# Mainsystem.net
KiCad netlist of a schematic drawn in Altium Designer
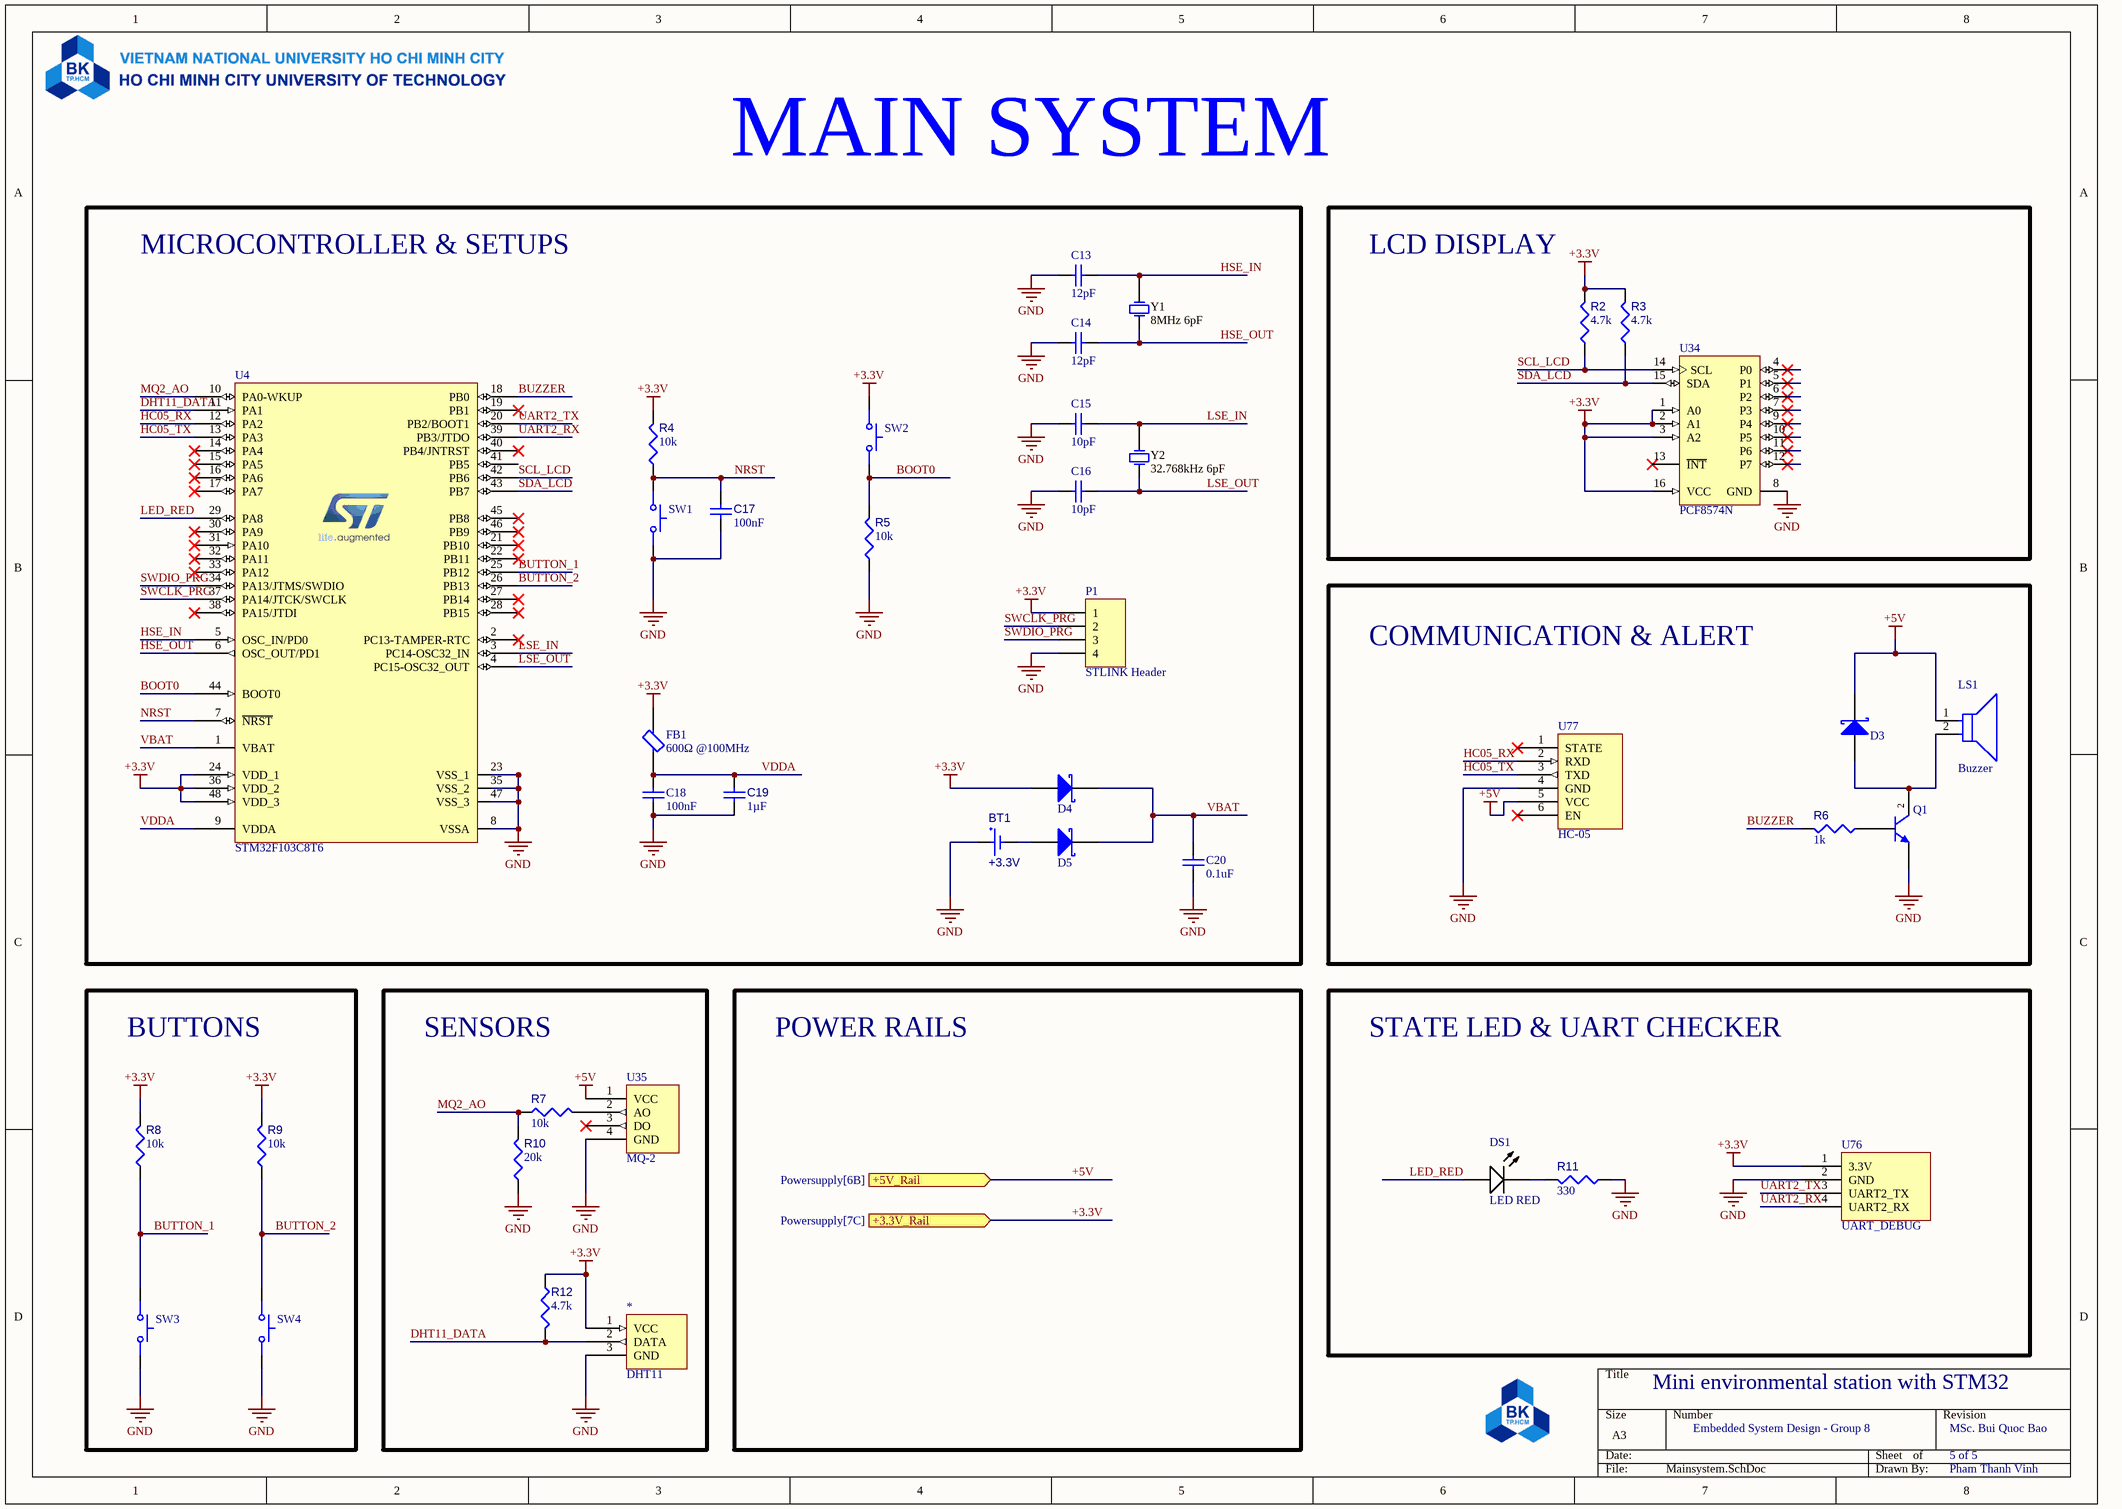
[diagram p0: Mainsystem.SchDoc]

(export (version "E")
  (design (tool "Eeschema 10.0.6"))
  (components
    (comp (ref "*")
      (value "DHT11")
      (footprint "HDR1X3")
      (description "vinh")
      (libsource (lib "HONG AN pham") (part "New symbol 1"))
    )
    (comp (ref "BT1")
      (value "+3.3V")
      (footprint "SEIK-MS621FE-FL11E-2_V")
      (description "MS Lihium Rechargeable Battery, 3 V, -20 to 60 degC, Tray")
      (libsource (lib "HONG AN pham") (part "CMP-00622-2"))
    )
    (comp (ref "C13")
      (value "12pF")
      (footprint "CAPC1608X90X35ML15T15")
      (description "Chip Capacitor, 1 uF, +/- 10%, 16 V, 0603 (1608 Metric)")
      (fields (field (name "TOLERANCE") "10%") (field (name "Comment") "Capacitor 1uF +/- 10% 16V 0603"))
      (libsource (lib "HONG AN pham") (part "CAP-NP-2"))
    )
    (comp (ref "C14")
      (value "12pF")
      (footprint "CAPC1608X90X35ML15T15")
      (description "Chip Capacitor, 1 uF, +/- 10%, 16 V, 0603 (1608 Metric)")
      (fields (field (name "TOLERANCE") "10%") (field (name "Comment") "Capacitor 1uF +/- 10% 16V 0603"))
      (libsource (lib "HONG AN pham") (part "CAP-NP-2"))
    )
    (comp (ref "C15")
      (value "10pF")
      (footprint "CAPC1608X90X35ML15T15")
      (description "Chip Capacitor, 1 uF, +/- 10%, 16 V, 0603 (1608 Metric)")
      (fields (field (name "TOLERANCE") "10%") (field (name "Comment") "Capacitor 1uF +/- 10% 16V 0603"))
      (libsource (lib "HONG AN pham") (part "CAP-NP-2"))
    )
    (comp (ref "C16")
      (value "10pF")
      (footprint "CAPC1608X90X35ML15T15")
      (description "Chip Capacitor, 1 uF, +/- 10%, 16 V, 0603 (1608 Metric)")
      (fields (field (name "TOLERANCE") "10%") (field (name "Comment") "Capacitor 1uF +/- 10% 16V 0603"))
      (libsource (lib "HONG AN pham") (part "CAP-NP-2"))
    )
    (comp (ref "C17")
      (value "100nF")
      (footprint "CAPC0402(1005)60_L")
      (description "Chip Capacitor, 100nF +/-20%, 10V, 0402, Thickness 0.6 mm")
      (fields (field (name "TOLERANCE") "20%") (field (name "Comment") "Capacitor 100nF +/-20% 10V 0402"))
      (libsource (lib "HONG AN pham") (part "CAP-NP-2"))
    )
    (comp (ref "C18")
      (value "100nF")
      (footprint "CAPC1608X90X35ML15T15")
      (description "Chip Capacitor, 1 uF, +/- 10%, 16 V, 0603 (1608 Metric)")
      (fields (field (name "TOLERANCE") "10%") (field (name "Comment") "Capacitor 1uF +/- 10% 16V 0603"))
      (libsource (lib "HONG AN pham") (part "CAP-NP-2"))
    )
    (comp (ref "C19")
      (value "1µF")
      (footprint "CAPC1608X90X35ML15T15")
      (description "Chip Capacitor, 1 uF, +/- 10%, 16 V, 0603 (1608 Metric)")
      (fields (field (name "TOLERANCE") "10%") (field (name "Comment") "Capacitor 1uF +/- 10% 16V 0603"))
      (libsource (lib "HONG AN pham") (part "CAP-NP-2"))
    )
    (comp (ref "C20")
      (value "0.1uF")
      (footprint "CAPC1608X90X35ML15T15")
      (description "Chip Capacitor, 1 uF, +/- 10%, 16 V, 0603 (1608 Metric)")
      (fields (field (name "TOLERANCE") "10%") (field (name "Comment") "Capacitor 1uF +/- 10% 16V 0603"))
      (libsource (lib "HONG AN pham") (part "CAP-NP-2"))
    )
    (comp (ref "D3")
      (value "B5819W")
      (footprint "MCC-SOD123_V")
      (description "Schottky Barrier Rectifier, 40 V, 1 A, -65 to 125 degC, 2-Pin SOD123, RoHS, Tape and Reel")
      (fields (field (name "MANUFACTURER") "Micro Commercial Components"))
      (libsource (lib "HONG AN pham") (part "DSKY-AK-2"))
    )
    (comp (ref "D4")
      (value "B5819W")
      (footprint "MCC-SOD123_V")
      (description "Schottky Barrier Rectifier, 40 V, 1 A, -65 to 125 degC, 2-Pin SOD123, RoHS, Tape and Reel")
      (fields (field (name "MANUFACTURER") "Micro Commercial Components"))
      (libsource (lib "HONG AN pham") (part "DSKY-AK-2"))
    )
    (comp (ref "D5")
      (value "B5819W")
      (footprint "MCC-SOD123_V")
      (description "Schottky Barrier Rectifier, 40 V, 1 A, -65 to 125 degC, 2-Pin SOD123, RoHS, Tape and Reel")
      (fields (field (name "MANUFACTURER") "Micro Commercial Components"))
      (libsource (lib "HONG AN pham") (part "DSKY-AK-2"))
    )
    (comp (ref "DS1")
      (value "LED RED")
      (footprint "EVRL-0402-2_V")
      (description "Chip LED, White, 5 V, 10 mA, 30 mW, -40 to 85 degC, 2-Pin SMD (0402), RoHS, Tape and Reel")
      (fields (field (name "POWER") "30mW") (field (name "MANUFACTURER") "Everlight Electronics"))
      (libsource (lib "HONG AN pham") (part "LED-WHITE-AK-2"))
    )
    (comp (ref "FB1")
      (value "600Ω @100MHz")
      (footprint "FP-BLM21-0_2-t0_85-e0_5-IPC_B")
      (description "Chip Ferrite Bead, 0805, 150Ω @ 100MHz, 0.21Ω, 25%, 600mA")
      (libsource (lib "Altium Content Vault") (part "5f30dd21d616792df468990f7003faa"))
    )
    (comp (ref "LS1")
      (value "Buzzer")
      (footprint "FP-CT-1205CL-SMT-TR-MFG")
      (libsource (lib "HONG AN pham") (part "1973c4b650225fd2ddacaff6b763965"))
    )
    (comp (ref "P1")
      (value "STLINK Header")
      (footprint "JP4")
      (description "Header, 4-Pin")
      (fields (field (name "PUBLISHER") "Altium Limited"))
      (libsource (lib "HONG AN pham") (part "Header 4H"))
    )
    (comp (ref "Q1")
      (value "MMBT2222A")
      (footprint "MMBT-SOT23")
      (description "TRANS NPN, 40V, 600MA, SOT23-3")
      (libsource (lib "HONG AN pham") (part "MMBT2222A"))
    )
    (comp (ref "R2")
      (value "4.7k")
      (footprint "RESC0402(1005)_L")
      (description "10K 0.063W 1% 0402 (1005 Metric)  SMD")
      (fields (field (name "POWER") "63mW") (field (name "TOLERANCE") "1%"))
      (libsource (lib "HONG AN pham") (part "10KR2F"))
    )
    (comp (ref "R3")
      (value "4.7k")
      (footprint "RESC0402(1005)_L")
      (description "10K 0.063W 1% 0402 (1005 Metric)  SMD")
      (fields (field (name "POWER") "63mW") (field (name "TOLERANCE") "1%"))
      (libsource (lib "HONG AN pham") (part "10KR2F"))
    )
    (comp (ref "R4")
      (value "10k")
      (footprint "RESC0402(1005)_L")
      (description "10K 0.063W 1% 0402 (1005 Metric)  SMD")
      (fields (field (name "POWER") "63mW") (field (name "TOLERANCE") "1%"))
      (libsource (lib "HONG AN pham") (part "10KR2F"))
    )
    (comp (ref "R5")
      (value "10k")
      (footprint "RESC0402(1005)_L")
      (description "10K 0.063W 1% 0402 (1005 Metric)  SMD")
      (fields (field (name "POWER") "63mW") (field (name "TOLERANCE") "1%"))
      (libsource (lib "HONG AN pham") (part "10KR2F"))
    )
    (comp (ref "R6")
      (value "1k")
      (footprint "RESC0402(1005)_L")
      (description "10K 0.063W 1% 0402 (1005 Metric)  SMD")
      (fields (field (name "POWER") "63mW") (field (name "TOLERANCE") "1%"))
      (libsource (lib "HONG AN pham") (part "10KR2F"))
    )
    (comp (ref "R7")
      (value "10k")
      (footprint "RESC0402(1005)_L")
      (description "10K 0.063W 1% 0402 (1005 Metric)  SMD")
      (fields (field (name "POWER") "63mW") (field (name "TOLERANCE") "1%"))
      (libsource (lib "HONG AN pham") (part "10KR2F"))
    )
    (comp (ref "R8")
      (value "10k")
      (footprint "RESC0402(1005)_L")
      (description "10K 0.063W 1% 0402 (1005 Metric)  SMD")
      (fields (field (name "POWER") "63mW") (field (name "TOLERANCE") "1%"))
      (libsource (lib "HONG AN pham") (part "10KR2F"))
    )
    (comp (ref "R9")
      (value "10k")
      (footprint "RESC0402(1005)_L")
      (description "10K 0.063W 1% 0402 (1005 Metric)  SMD")
      (fields (field (name "POWER") "63mW") (field (name "TOLERANCE") "1%"))
      (libsource (lib "HONG AN pham") (part "10KR2F"))
    )
    (comp (ref "R10")
      (value "20k")
      (footprint "RESC0402(1005)_L")
      (description "10K 0.063W 1% 0402 (1005 Metric)  SMD")
      (fields (field (name "POWER") "63mW") (field (name "TOLERANCE") "1%"))
      (libsource (lib "HONG AN pham") (part "10KR2F"))
    )
    (comp (ref "R11")
      (value "330")
      (footprint "RESC0402(1005)_L")
      (description "10K 0.063W 1% 0402 (1005 Metric)  SMD")
      (fields (field (name "POWER") "63mW") (field (name "TOLERANCE") "1%"))
      (libsource (lib "HONG AN pham") (part "10KR2F"))
    )
    (comp (ref "R12")
      (value "4.7k")
      (footprint "RESC0402(1005)_L")
      (description "10K 0.063W 1% 0402 (1005 Metric)  SMD")
      (fields (field (name "POWER") "63mW") (field (name "TOLERANCE") "1%"))
      (libsource (lib "HONG AN pham") (part "10KR2F"))
    )
    (comp (ref "SW1")
      (value "B3U-1000P-B")
      (footprint "OMRON-B3U-1000P-2-B_V")
      (libsource (lib "HONG AN pham") (part "CMP-00164-6"))
    )
    (comp (ref "SW2")
      (value "B3U-1000P-B")
      (footprint "OMRON-B3U-1000P-2-B_V")
      (libsource (lib "HONG AN pham") (part "CMP-00164-6"))
    )
    (comp (ref "SW3")
      (value "B3U-1000P-B")
      (footprint "OMRON-B3U-1000P-2-B_V")
      (libsource (lib "HONG AN pham") (part "CMP-00164-6"))
    )
    (comp (ref "SW4")
      (value "B3U-1000P-B")
      (footprint "OMRON-B3U-1000P-2-B_V")
      (libsource (lib "HONG AN pham") (part "CMP-00164-6"))
    )
    (comp (ref "U4")
      (value "STM32F103C8T6")
      (footprint "STM32F103C8T6")
      (description "ARM Microcontrollers - MCU 32BIT Cortex M3 64KB 20KB RAM 2X12 ADC")
      (fields (field (name "MANUFACTURER") "STM"))
      (libsource (lib "HONG AN pham") (part "STM32F103C8T6"))
    )
    (comp (ref "U34")
      (value "PCF8574N")
      (footprint "N0016A")
      (description "8-bit 2.5- to 5.5-V I2C/SMBus I/O expander with interrupt 16-PDIP -40 to 85")
      (libsource (lib "HONG AN pham") (part "TI-PCF8574-PDIP_N-16"))
    )
    (comp (ref "U35")
      (value "MQ-2")
      (footprint "HDR1X4")
      (description "Gas sensor")
      (libsource (lib "HONG AN pham") (part "MQ-2-Symbol-1"))
    )
    (comp (ref "U76")
      (value "UART_DEBUG")
      (footprint "HDR1X4")
      (description "USB-to-UART TTL adapter.")
      (libsource (lib "") (part "New symbol 1_1"))
    )
    (comp (ref "U77")
      (value "HC-05")
      (footprint "HDR1X6")
      (description "Bluetooth module with UART communication")
      (libsource (lib "HONG AN pham") (part "HC-05-Symbol-1"))
    )
    (comp (ref "Y1")
      (value "8MHz 6pF")
      (footprint "FOX-HC49SDLF_V")
      (description "Resistance Weld Crystal, 8 MHz, +/- 30 ppm, 20 pF, -20 to 70 degC, 2-Pin SMD, RoHS, Tape and Reel")
      (fields (field (name "MANUFACTURER") "FOX Electronics") (field (name "TOLERANCE") "50ppm"))
      (libsource (lib "HONG AN pham") (part "XTAL-1-2-2"))
    )
    (comp (ref "Y2")
      (value "32.768kHz 6pF")
      (footprint "FOX-HC49SDLF_V")
      (description "Resistance Weld Crystal, 8 MHz, +/- 30 ppm, 20 pF, -20 to 70 degC, 2-Pin SMD, RoHS, Tape and Reel")
      (fields (field (name "MANUFACTURER") "FOX Electronics") (field (name "TOLERANCE") "50ppm"))
      (libsource (lib "HONG AN pham") (part "XTAL-1-2-2"))
    )
  )
  (nets
    (net (code "1") (name "+3.3V") (class "Default")
      (node (ref "*") (pin "1") (pinfunction "VCC_1") (pintype "input"))
      (node (ref "D4") (pin "1") (pinfunction "A_1") (pintype "passive"))
      (node (ref "FB1") (pin "2") (pinfunction "2_2") (pintype "passive"))
      (node (ref "P1") (pin "1") (pinfunction "1_1") (pintype "passive"))
      (node (ref "R12") (pin "1") (pinfunction "1_1") (pintype "passive"))
      (node (ref "R2") (pin "2") (pinfunction "2_2") (pintype "passive"))
      (node (ref "R3") (pin "2") (pinfunction "2_2") (pintype "passive"))
      (node (ref "R4") (pin "2") (pinfunction "2_2") (pintype "passive"))
      (node (ref "R8") (pin "2") (pinfunction "2_2") (pintype "passive"))
      (node (ref "R9") (pin "2") (pinfunction "2_2") (pintype "passive"))
      (node (ref "SW2") (pin "1") (pinfunction "1_1") (pintype "passive"))
      (node (ref "U34") (pin "1") (pinfunction "A0_1") (pintype "input"))
      (node (ref "U34") (pin "16") (pinfunction "VCC_16") (pintype "input"))
      (node (ref "U34") (pin "2") (pinfunction "A1_2") (pintype "input"))
      (node (ref "U34") (pin "3") (pinfunction "A2_3") (pintype "input"))
      (node (ref "U4") (pin "24") (pinfunction "VDD_1_24") (pintype "input"))
      (node (ref "U4") (pin "36") (pinfunction "VDD_2_36") (pintype "input"))
      (node (ref "U4") (pin "48") (pinfunction "VDD_3_48") (pintype "input"))
      (node (ref "U76") (pin "1") (pinfunction "3.3V_1") (pintype "passive"))
    )
    (net (code "2") (name "+5V") (class "Default")
      (node (ref "D3") (pin "2") (pinfunction "K_2") (pintype "passive"))
      (node (ref "LS1") (pin "1") (pinfunction "C_1") (pintype "passive"))
      (node (ref "U35") (pin "1") (pinfunction "VCC_1") (pintype "passive"))
      (node (ref "U77") (pin "5") (pinfunction "VCC_5") (pintype "passive"))
    )
    (net (code "3") (name "/BOOT0") (class "Default")
      (node (ref "R5") (pin "2") (pinfunction "2_2") (pintype "passive"))
      (node (ref "SW2") (pin "2") (pinfunction "2_2") (pintype "passive"))
      (node (ref "U4") (pin "44") (pinfunction "BOOT0_44") (pintype "input"))
    )
    (net (code "4") (name "/BUTTON_1") (class "Default")
      (node (ref "R8") (pin "1") (pinfunction "1_1") (pintype "passive"))
      (node (ref "SW3") (pin "1") (pinfunction "1_1") (pintype "passive"))
      (node (ref "U4") (pin "25") (pinfunction "PB12_25") (pintype "bidirectional"))
    )
    (net (code "5") (name "/BUTTON_2") (class "Default")
      (node (ref "R9") (pin "1") (pinfunction "1_1") (pintype "passive"))
      (node (ref "SW4") (pin "1") (pinfunction "1_1") (pintype "passive"))
      (node (ref "U4") (pin "26") (pinfunction "PB13_26") (pintype "bidirectional"))
    )
    (net (code "6") (name "/BUZZER") (class "Default")
      (node (ref "R6") (pin "2") (pinfunction "2_2") (pintype "passive"))
      (node (ref "U4") (pin "18") (pinfunction "PB0_18") (pintype "bidirectional"))
    )
    (net (code "7") (name "/DHT11_DATA") (class "Default")
      (node (ref "*") (pin "2") (pinfunction "DATA_2") (pintype "output"))
      (node (ref "R12") (pin "2") (pinfunction "2_2") (pintype "passive"))
      (node (ref "U4") (pin "11") (pinfunction "PA1_11") (pintype "input"))
    )
    (net (code "8") (name "/HC05_RX") (class "Default")
      (node (ref "U4") (pin "12") (pinfunction "PA2_12") (pintype "bidirectional"))
      (node (ref "U77") (pin "2") (pinfunction "RXD_2") (pintype "input"))
    )
    (net (code "9") (name "/HC05_TX") (class "Default")
      (node (ref "U4") (pin "13") (pinfunction "PA3_13") (pintype "bidirectional"))
      (node (ref "U77") (pin "3") (pinfunction "TXD_3") (pintype "output"))
    )
    (net (code "10") (name "/HSE_IN") (class "Default")
      (node (ref "C13") (pin "2") (pinfunction "2_2") (pintype "passive"))
      (node (ref "U4") (pin "5") (pinfunction "OSC_IN/PD0_5") (pintype "input"))
      (node (ref "Y1") (pin "1") (pinfunction "1_1") (pintype "passive"))
    )
    (net (code "11") (name "/HSE_OUT") (class "Default")
      (node (ref "C14") (pin "2") (pinfunction "2_2") (pintype "passive"))
      (node (ref "U4") (pin "6") (pinfunction "OSC_OUT/PD1_6") (pintype "output"))
      (node (ref "Y1") (pin "2") (pinfunction "2_2") (pintype "passive"))
    )
    (net (code "12") (name "/LED_RED") (class "Default")
      (node (ref "DS1") (pin "1") (pinfunction "A_1") (pintype "passive"))
      (node (ref "U4") (pin "29") (pinfunction "PA8_29") (pintype "bidirectional"))
    )
    (net (code "13") (name "/LSE_IN") (class "Default")
      (node (ref "C15") (pin "2") (pinfunction "2_2") (pintype "passive"))
      (node (ref "U4") (pin "3") (pinfunction "PC14-OSC32_IN_3") (pintype "bidirectional"))
      (node (ref "Y2") (pin "1") (pinfunction "1_1") (pintype "passive"))
    )
    (net (code "14") (name "/LSE_OUT") (class "Default")
      (node (ref "C16") (pin "2") (pinfunction "2_2") (pintype "passive"))
      (node (ref "U4") (pin "4") (pinfunction "PC15-OSC32_OUT_4") (pintype "bidirectional"))
      (node (ref "Y2") (pin "2") (pinfunction "2_2") (pintype "passive"))
    )
    (net (code "15") (name "/MQ2_AO") (class "Default")
      (node (ref "R10") (pin "2") (pinfunction "2_2") (pintype "passive"))
      (node (ref "R7") (pin "1") (pinfunction "1_1") (pintype "passive"))
      (node (ref "U4") (pin "10") (pinfunction "PA0-WKUP_10") (pintype "bidirectional"))
    )
    (net (code "16") (name "/NRST") (class "Default")
      (node (ref "C17") (pin "2") (pinfunction "2_2") (pintype "passive"))
      (node (ref "R4") (pin "1") (pinfunction "1_1") (pintype "passive"))
      (node (ref "SW1") (pin "1") (pinfunction "1_1") (pintype "passive"))
      (node (ref "U4") (pin "7") (pinfunction "~{NRST}_7") (pintype "bidirectional"))
    )
    (net (code "17") (name "/SCL_LCD") (class "Default")
      (node (ref "R2") (pin "1") (pinfunction "1_1") (pintype "passive"))
      (node (ref "U34") (pin "14") (pinfunction "SCL_14") (pintype "input"))
      (node (ref "U4") (pin "42") (pinfunction "PB6_42") (pintype "bidirectional"))
    )
    (net (code "18") (name "/SDA_LCD") (class "Default")
      (node (ref "R3") (pin "1") (pinfunction "1_1") (pintype "passive"))
      (node (ref "U34") (pin "15") (pinfunction "SDA_15") (pintype "bidirectional"))
      (node (ref "U4") (pin "43") (pinfunction "PB7_43") (pintype "bidirectional"))
    )
    (net (code "19") (name "/SWCLK_PRG") (class "Default")
      (node (ref "P1") (pin "2") (pinfunction "2_2") (pintype "passive"))
      (node (ref "U4") (pin "37") (pinfunction "PA14/JTCK/SWCLK_37") (pintype "bidirectional"))
    )
    (net (code "20") (name "/SWDIO_PRG") (class "Default")
      (node (ref "P1") (pin "3") (pinfunction "3_3") (pintype "passive"))
      (node (ref "U4") (pin "34") (pinfunction "PA13/JTMS/SWDIO_34") (pintype "bidirectional"))
    )
    (net (code "21") (name "/UART2_RX") (class "Default")
      (node (ref "U4") (pin "39") (pinfunction "PB3/JTDO_39") (pintype "bidirectional"))
      (node (ref "U76") (pin "4") (pinfunction "UART2_RX_4") (pintype "passive"))
    )
    (net (code "22") (name "/UART2_TX") (class "Default")
      (node (ref "U4") (pin "20") (pinfunction "PB2/BOOT1_20") (pintype "bidirectional"))
      (node (ref "U76") (pin "3") (pinfunction "UART2_TX_3") (pintype "passive"))
    )
    (net (code "23") (name "/VBAT") (class "Default")
      (node (ref "C20") (pin "2") (pinfunction "2_2") (pintype "passive"))
      (node (ref "D4") (pin "2") (pinfunction "K_2") (pintype "passive"))
      (node (ref "D5") (pin "2") (pinfunction "K_2") (pintype "passive"))
      (node (ref "U4") (pin "1") (pinfunction "VBAT_1") (pintype "power_in"))
    )
    (net (code "24") (name "/VDDA") (class "Default")
      (node (ref "C18") (pin "2") (pinfunction "2_2") (pintype "passive"))
      (node (ref "C19") (pin "2") (pinfunction "2_2") (pintype "passive"))
      (node (ref "FB1") (pin "1") (pinfunction "1_1") (pintype "passive"))
      (node (ref "U4") (pin "9") (pinfunction "VDDA_9") (pintype "power_in"))
    )
    (net (code "25") (name "GND") (class "Default")
      (node (ref "*") (pin "3") (pinfunction "GND_3") (pintype "power_in"))
      (node (ref "BT1") (pin "1") (pinfunction "+_1") (pintype "passive"))
      (node (ref "C13") (pin "1") (pinfunction "1_1") (pintype "passive"))
      (node (ref "C14") (pin "1") (pinfunction "1_1") (pintype "passive"))
      (node (ref "C15") (pin "1") (pinfunction "1_1") (pintype "passive"))
      (node (ref "C16") (pin "1") (pinfunction "1_1") (pintype "passive"))
      (node (ref "C17") (pin "1") (pinfunction "1_1") (pintype "passive"))
      (node (ref "C18") (pin "1") (pinfunction "1_1") (pintype "passive"))
      (node (ref "C19") (pin "1") (pinfunction "1_1") (pintype "passive"))
      (node (ref "C20") (pin "1") (pinfunction "1_1") (pintype "passive"))
      (node (ref "P1") (pin "4") (pinfunction "4_4") (pintype "passive"))
      (node (ref "Q1") (pin "3") (pinfunction "E_3") (pintype "passive"))
      (node (ref "R10") (pin "1") (pinfunction "1_1") (pintype "passive"))
      (node (ref "R11") (pin "1") (pinfunction "1_1") (pintype "passive"))
      (node (ref "R5") (pin "1") (pinfunction "1_1") (pintype "passive"))
      (node (ref "SW1") (pin "2") (pinfunction "2_2") (pintype "passive"))
      (node (ref "SW3") (pin "2") (pinfunction "2_2") (pintype "passive"))
      (node (ref "SW4") (pin "2") (pinfunction "2_2") (pintype "passive"))
      (node (ref "U34") (pin "8") (pinfunction "GND_8") (pintype "power_in"))
      (node (ref "U35") (pin "4") (pinfunction "GND_4") (pintype "passive"))
      (node (ref "U4") (pin "23") (pinfunction "VSS_1_23") (pintype "power_in"))
      (node (ref "U4") (pin "35") (pinfunction "VSS_2_35") (pintype "power_in"))
      (node (ref "U4") (pin "47") (pinfunction "VSS_3_47") (pintype "power_in"))
      (node (ref "U4") (pin "8") (pinfunction "VSSA_8") (pintype "power_in"))
      (node (ref "U76") (pin "2") (pinfunction "GND_2") (pintype "passive"))
      (node (ref "U77") (pin "4") (pinfunction "GND_4") (pintype "passive"))
    )
    (net (code "26") (name "Net-(BT1--)") (class "Default")
      (node (ref "BT1") (pin "2") (pinfunction "-_2") (pintype "passive"))
      (node (ref "D5") (pin "1") (pinfunction "A_1") (pintype "passive"))
    )
    (net (code "27") (name "Net-(D3-A)") (class "Default")
      (node (ref "D3") (pin "1") (pinfunction "A_1") (pintype "passive"))
      (node (ref "LS1") (pin "2") (pinfunction "A_2") (pintype "passive"))
      (node (ref "Q1") (pin "2") (pinfunction "C_2") (pintype "passive"))
    )
    (net (code "28") (name "Net-(DS1-K)") (class "Default")
      (node (ref "DS1") (pin "2") (pinfunction "K_2") (pintype "passive"))
      (node (ref "R11") (pin "2") (pinfunction "2_2") (pintype "passive"))
    )
    (net (code "29") (name "Net-(Q1-B)") (class "Default")
      (node (ref "Q1") (pin "1") (pinfunction "B_1") (pintype "passive"))
      (node (ref "R6") (pin "1") (pinfunction "1_1") (pintype "passive"))
    )
    (net (code "30") (name "Net-(U35-AO)") (class "Default")
      (node (ref "R7") (pin "2") (pinfunction "2_2") (pintype "passive"))
      (node (ref "U35") (pin "2") (pinfunction "AO_2") (pintype "output"))
    )
    (net (code "31") (name "unconnected-(U4-PA4-Pad14)") (class "Default")
      (node (ref "U4") (pin "14") (pinfunction "PA4_14") (pintype "bidirectional+no_connect"))
    )
    (net (code "32") (name "unconnected-(U4-PA5-Pad15)") (class "Default")
      (node (ref "U4") (pin "15") (pinfunction "PA5_15") (pintype "bidirectional+no_connect"))
    )
    (net (code "33") (name "unconnected-(U4-PA6-Pad16)") (class "Default")
      (node (ref "U4") (pin "16") (pinfunction "PA6_16") (pintype "bidirectional+no_connect"))
    )
    (net (code "34") (name "unconnected-(U4-PA7-Pad17)") (class "Default")
      (node (ref "U4") (pin "17") (pinfunction "PA7_17") (pintype "bidirectional+no_connect"))
    )
    (net (code "35") (name "unconnected-(U4-PA9-Pad30)") (class "Default")
      (node (ref "U4") (pin "30") (pinfunction "PA9_30") (pintype "bidirectional+no_connect"))
    )
    (net (code "36") (name "unconnected-(U4-PA10-Pad31)") (class "Default")
      (node (ref "U4") (pin "31") (pinfunction "PA10_31") (pintype "input+no_connect"))
    )
    (net (code "37") (name "unconnected-(U4-PA11-Pad32)") (class "Default")
      (node (ref "U4") (pin "32") (pinfunction "PA11_32") (pintype "bidirectional+no_connect"))
    )
    (net (code "38") (name "unconnected-(U4-PA12-Pad33)") (class "Default")
      (node (ref "U4") (pin "33") (pinfunction "PA12_33") (pintype "bidirectional+no_connect"))
    )
    (net (code "39") (name "unconnected-(U4-PA15{slash}JTDI-Pad38)") (class "Default")
      (node (ref "U4") (pin "38") (pinfunction "PA15/JTDI_38") (pintype "bidirectional+no_connect"))
    )
    (net (code "40") (name "unconnected-(U4-PB1-Pad19)") (class "Default")
      (node (ref "U4") (pin "19") (pinfunction "PB1_19") (pintype "bidirectional+no_connect"))
    )
    (net (code "41") (name "unconnected-(U4-PB4{slash}JNTRST-Pad40)") (class "Default")
      (node (ref "U4") (pin "40") (pinfunction "PB4/JNTRST_40") (pintype "bidirectional+no_connect"))
    )
    (net (code "42") (name "unconnected-(U4-PB5-Pad41)") (class "Default")
      (node (ref "U4") (pin "41") (pinfunction "PB5_41") (pintype "bidirectional"))
    )
    (net (code "43") (name "unconnected-(U4-PB8-Pad45)") (class "Default")
      (node (ref "U4") (pin "45") (pinfunction "PB8_45") (pintype "bidirectional+no_connect"))
    )
    (net (code "44") (name "unconnected-(U4-PB9-Pad46)") (class "Default")
      (node (ref "U4") (pin "46") (pinfunction "PB9_46") (pintype "bidirectional+no_connect"))
    )
    (net (code "45") (name "unconnected-(U4-PB10-Pad21)") (class "Default")
      (node (ref "U4") (pin "21") (pinfunction "PB10_21") (pintype "bidirectional+no_connect"))
    )
    (net (code "46") (name "unconnected-(U4-PB11-Pad22)") (class "Default")
      (node (ref "U4") (pin "22") (pinfunction "PB11_22") (pintype "bidirectional+no_connect"))
    )
    (net (code "47") (name "unconnected-(U4-PB14-Pad27)") (class "Default")
      (node (ref "U4") (pin "27") (pinfunction "PB14_27") (pintype "bidirectional+no_connect"))
    )
    (net (code "48") (name "unconnected-(U4-PB15-Pad28)") (class "Default")
      (node (ref "U4") (pin "28") (pinfunction "PB15_28") (pintype "bidirectional+no_connect"))
    )
    (net (code "49") (name "unconnected-(U4-PC13-TAMPER-RTC-Pad2)") (class "Default")
      (node (ref "U4") (pin "2") (pinfunction "PC13-TAMPER-RTC_2") (pintype "bidirectional+no_connect"))
    )
    (net (code "50") (name "unconnected-(U34-P0-Pad4)") (class "Default")
      (node (ref "U34") (pin "4") (pinfunction "P0_4") (pintype "bidirectional+no_connect"))
    )
    (net (code "51") (name "unconnected-(U34-P1-Pad5)") (class "Default")
      (node (ref "U34") (pin "5") (pinfunction "P1_5") (pintype "bidirectional+no_connect"))
    )
    (net (code "52") (name "unconnected-(U34-P2-Pad6)") (class "Default")
      (node (ref "U34") (pin "6") (pinfunction "P2_6") (pintype "bidirectional+no_connect"))
    )
    (net (code "53") (name "unconnected-(U34-P3-Pad7)") (class "Default")
      (node (ref "U34") (pin "7") (pinfunction "P3_7") (pintype "bidirectional+no_connect"))
    )
    (net (code "54") (name "unconnected-(U34-P4-Pad9)") (class "Default")
      (node (ref "U34") (pin "9") (pinfunction "P4_9") (pintype "bidirectional+no_connect"))
    )
    (net (code "55") (name "unconnected-(U34-P5-Pad10)") (class "Default")
      (node (ref "U34") (pin "10") (pinfunction "P5_10") (pintype "bidirectional+no_connect"))
    )
    (net (code "56") (name "unconnected-(U34-P6-Pad11)") (class "Default")
      (node (ref "U34") (pin "11") (pinfunction "P6_11") (pintype "bidirectional+no_connect"))
    )
    (net (code "57") (name "unconnected-(U34-P7-Pad12)") (class "Default")
      (node (ref "U34") (pin "12") (pinfunction "P7_12") (pintype "bidirectional+no_connect"))
    )
    (net (code "58") (name "unconnected-(U34-~{INT}-Pad13)") (class "Default")
      (node (ref "U34") (pin "13") (pinfunction "~{INT}_13") (pintype "open_collector+no_connect"))
    )
    (net (code "59") (name "unconnected-(U35-DO-Pad3)") (class "Default")
      (node (ref "U35") (pin "3") (pinfunction "DO_3") (pintype "output+no_connect"))
    )
    (net (code "60") (name "unconnected-(U77-EN-Pad6)") (class "Default")
      (node (ref "U77") (pin "6") (pinfunction "EN_6") (pintype "passive+no_connect"))
    )
    (net (code "61") (name "unconnected-(U77-STATE-Pad1)") (class "Default")
      (node (ref "U77") (pin "1") (pinfunction "STATE_1") (pintype "passive+no_connect"))
    )
  )
)
